# Sheet1.net
KiCad netlist of a schematic drawn in Altium Designer
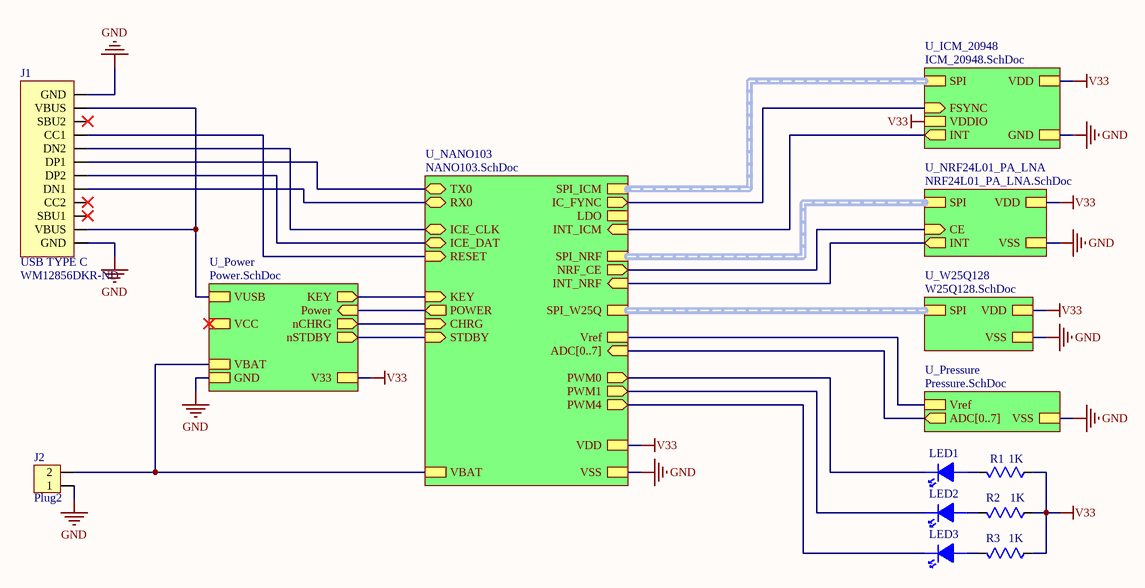
[diagram p0: Sheet1.SchDoc]

(export (version "E")
  (design (tool "Eeschema 10.0.6"))
  (components
    (comp (ref "J1")
      (value "USB TYPE C")
      (footprint "USBC-SMD16F")
      (description "USB Shielded I/O Receptacle; Type C; Right Angle; Surface Mount; Gold over Nickel")
      (fields
        (field (name "MANUFACTURER") "Molex")
        (field (name "MANUFACTURER PART NUMBER") "105450-0101")
        (field (name "SUPPLIER PART NUMBER 1") "WM12856DKR-ND")
      )
      (libsource (lib "ZGR") (part "USB TYPE C"))
    )
    (comp (ref "J2")
      (value "Plug2")
      (footprint "Terminal_block_2pin_1.25mm_SMD")
      (libsource (lib "ZGR") (part "Plug2"))
    )
    (comp (ref "LED1") (value "LED") (footprint "SMD-0603_LED") (libsource (lib "ZGR") (part "LED")))
    (comp (ref "LED2") (value "LED") (footprint "SMD-0603_LED") (libsource (lib "ZGR") (part "LED")))
    (comp (ref "LED3") (value "LED") (footprint "SMD-0603_LED") (libsource (lib "ZGR") (part "LED")))
    (comp (ref "R1")
      (value "1K")
      (footprint "RES_0402")
      (fields (field (name "Comment") "Res"))
      (libsource (lib "ZGR") (part "Res"))
    )
    (comp (ref "R2")
      (value "1K")
      (footprint "RES_0402")
      (fields (field (name "Comment") "Res"))
      (libsource (lib "ZGR") (part "Res"))
    )
    (comp (ref "R3")
      (value "1K")
      (footprint "RES_0402")
      (fields (field (name "Comment") "Res"))
      (libsource (lib "ZGR") (part "Res"))
    )
  )
  (nets
    (net (code "2") (name "/ICE_CLK") (class "Default")
      (node (ref "J1") (pin "5") (pinfunction "DN2_5") (pintype "passive"))
    )
    (net (code "3") (name "/ICE_DAT") (class "Default")
      (node (ref "J1") (pin "7") (pinfunction "DP2_7") (pintype "passive"))
    )
    (net (code "11") (name "/PWM0") (class "Default")
      (node (ref "LED1") (pin "2") (pinfunction "2_2") (pintype "passive"))
    )
    (net (code "12") (name "/PWM1") (class "Default")
      (node (ref "LED2") (pin "2") (pinfunction "2_2") (pintype "passive"))
    )
    (net (code "13") (name "/PWM4") (class "Default")
      (node (ref "LED3") (pin "2") (pinfunction "2_2") (pintype "passive"))
    )
    (net (code "14") (name "/RESET") (class "Default")
      (node (ref "J1") (pin "4") (pinfunction "CC1_4") (pintype "passive"))
    )
    (net (code "15") (name "/RX0") (class "Default")
      (node (ref "J1") (pin "8") (pinfunction "DN1_8") (pintype "passive"))
    )
    (net (code "19") (name "/TX0") (class "Default")
      (node (ref "J1") (pin "6") (pinfunction "DP1_6") (pintype "passive"))
    )
    (net (code "20") (name "/VBAT") (class "Default")
      (node (ref "J2") (pin "2") (pinfunction "2_2") (pintype "passive"))
    )
    (net (code "22") (name "/VUSB") (class "Default")
      (node (ref "J1") (pin "11") (pinfunction "VBUS_11") (pintype "passive"))
      (node (ref "J1") (pin "2") (pinfunction "VBUS_2") (pintype "passive"))
    )
    (net (code "26") (name "GND") (class "Default")
      (node (ref "J1") (pin "1") (pinfunction "GND_1") (pintype "passive"))
      (node (ref "J1") (pin "12") (pinfunction "GND_12") (pintype "passive"))
      (node (ref "J2") (pin "1") (pinfunction "1_1") (pintype "passive"))
    )
    (net (code "27") (name "Net-(LED1-Pad1)") (class "Default")
      (node (ref "LED1") (pin "1") (pinfunction "1_1") (pintype "passive"))
      (node (ref "R1") (pin "1") (pinfunction "1_1") (pintype "passive"))
    )
    (net (code "28") (name "Net-(LED2-Pad1)") (class "Default")
      (node (ref "LED2") (pin "1") (pinfunction "1_1") (pintype "passive"))
      (node (ref "R2") (pin "1") (pinfunction "1_1") (pintype "passive"))
    )
    (net (code "29") (name "Net-(LED3-Pad1)") (class "Default")
      (node (ref "LED3") (pin "1") (pinfunction "1_1") (pintype "passive"))
      (node (ref "R3") (pin "1") (pinfunction "1_1") (pintype "passive"))
    )
    (net (code "30") (name "V33") (class "Default")
      (node (ref "R1") (pin "2") (pinfunction "2_2") (pintype "passive"))
      (node (ref "R2") (pin "2") (pinfunction "2_2") (pintype "passive"))
      (node (ref "R3") (pin "2") (pinfunction "2_2") (pintype "passive"))
    )
    (net (code "31") (name "unconnected-(J1-CC2-Pad9)") (class "Default")
      (node (ref "J1") (pin "9") (pinfunction "CC2_9") (pintype "passive+no_connect"))
    )
    (net (code "32") (name "unconnected-(J1-SBU1-Pad10)") (class "Default")
      (node (ref "J1") (pin "10") (pinfunction "SBU1_10") (pintype "passive+no_connect"))
    )
    (net (code "33") (name "unconnected-(J1-SBU2-Pad3)") (class "Default")
      (node (ref "J1") (pin "3") (pinfunction "SBU2_3") (pintype "passive+no_connect"))
    )
  )
)
